# DSP.net
KiCad netlist of a schematic drawn in Altium Designer
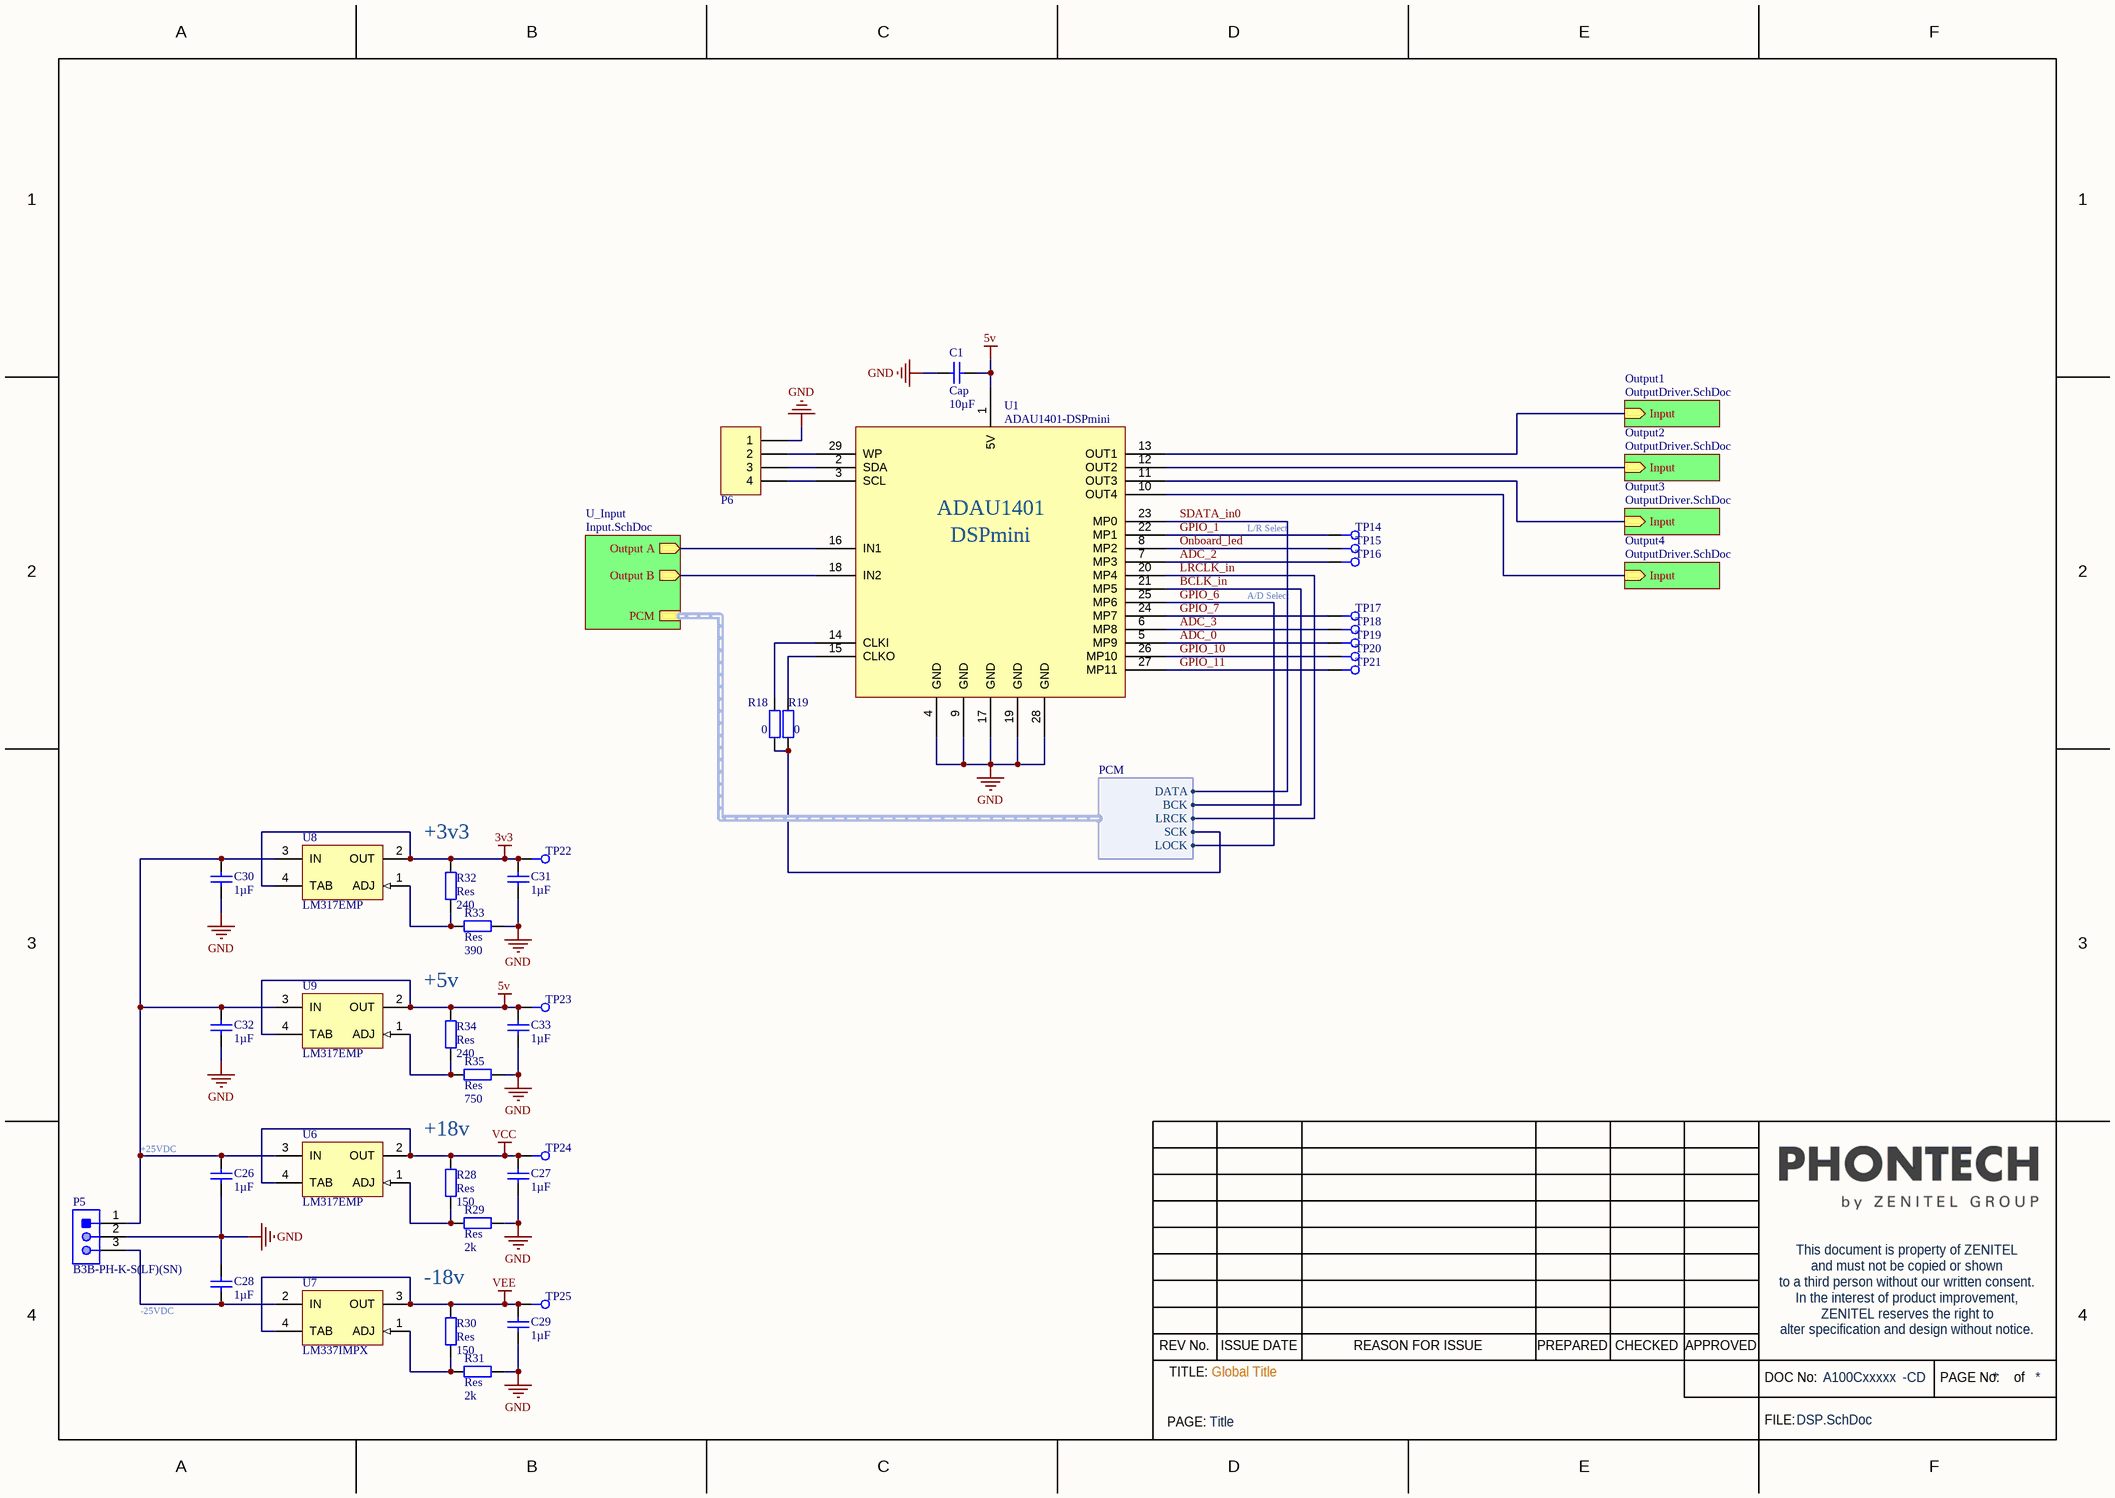
[diagram p0: DSP.SchDoc]

(export (version "E")
  (design (tool "Eeschema 10.0.6"))
  (components
    (comp (ref "C1")
      (value "Cap")
      (footprint "CAPC2013X140X50NL20T25")
      (description "CR0805 10u 10V X7R 10% h=1.25mm")
      (fields
        (field (name "ALTIUM_VALUE") "10µF")
        (field (name "TOLERANCE") "10%")
        (field (name "VOLTAGE") "10V")
      )
      (libsource (lib "Zenitel Concord PRO Vault") (part "Capacitor-IEC"))
    )
    (comp (ref "C26")
      (value "1µF")
      (footprint "CAPC3225N")
      (description "Chip cap 1uF 50v X7R 1210")
      (fields (field (name "TOLERANCE") "10%") (field (name "ZENITEL PARTNUMBER") "4000084277"))
      (libsource (lib "Zenitel Concord PRO Vault") (part "Capacitor-IEC"))
    )
    (comp (ref "C27")
      (value "1µF")
      (footprint "CAPC3225N")
      (description "Chip cap 1uF 50v X7R 1210")
      (fields (field (name "TOLERANCE") "10%") (field (name "ZENITEL PARTNUMBER") "4000084277"))
      (libsource (lib "Zenitel Concord PRO Vault") (part "Capacitor-IEC"))
    )
    (comp (ref "C28")
      (value "1µF")
      (footprint "CAPC3225N")
      (description "Chip cap 1uF 50v X7R 1210")
      (fields (field (name "TOLERANCE") "10%") (field (name "ZENITEL PARTNUMBER") "4000084277"))
      (libsource (lib "Zenitel Concord PRO Vault") (part "Capacitor-IEC"))
    )
    (comp (ref "C29")
      (value "1µF")
      (footprint "CAPC3225N")
      (description "Chip cap 1uF 50v X7R 1210")
      (fields (field (name "TOLERANCE") "10%") (field (name "ZENITEL PARTNUMBER") "4000084277"))
      (libsource (lib "Zenitel Concord PRO Vault") (part "Capacitor-IEC"))
    )
    (comp (ref "C30")
      (value "1µF")
      (footprint "CAPC3225N")
      (description "Chip cap 1uF 50v X7R 1210")
      (fields (field (name "TOLERANCE") "10%") (field (name "ZENITEL PARTNUMBER") "4000084277"))
      (libsource (lib "Zenitel Concord PRO Vault") (part "Capacitor-IEC"))
    )
    (comp (ref "C31")
      (value "1µF")
      (footprint "CAPC3225N")
      (description "Chip cap 1uF 50v X7R 1210")
      (fields (field (name "TOLERANCE") "10%") (field (name "ZENITEL PARTNUMBER") "4000084277"))
      (libsource (lib "Zenitel Concord PRO Vault") (part "Capacitor-IEC"))
    )
    (comp (ref "C32")
      (value "1µF")
      (footprint "CAPC3225N")
      (description "Chip cap 1uF 50v X7R 1210")
      (fields (field (name "TOLERANCE") "10%") (field (name "ZENITEL PARTNUMBER") "4000084277"))
      (libsource (lib "Zenitel Concord PRO Vault") (part "Capacitor-IEC"))
    )
    (comp (ref "C33")
      (value "1µF")
      (footprint "CAPC3225N")
      (description "Chip cap 1uF 50v X7R 1210")
      (fields (field (name "TOLERANCE") "10%") (field (name "ZENITEL PARTNUMBER") "4000084277"))
      (libsource (lib "Zenitel Concord PRO Vault") (part "Capacitor-IEC"))
    )
    (comp (ref "P5")
      (value "B3B-PH-K-S(LF)(SN)")
      (footprint "JST-B3B-PH-K-S-3_V")
      (fields (field (name "MANUFACTURER") "JST"))
      (libsource (lib "Altium Content Vault") (part "CN-1P-M-R3"))
    )
    (comp (ref "P6")
      (value "Header 4")
      (footprint "TSW-104-14-S-S")
      (description "4 Pin straight header")
      (fields (field (name "ZENITEL PARTNUMBER") "4000097756"))
      (libsource (lib "Zenitel Concord PRO Vault") (part "Header 4"))
    )
    (comp (ref "R18")
      (value "0")
      (footprint "RESC3216X60X45NL10T20")
      (description "0R 1206")
      (fields (field (name "ZENITEL PARTNUMBER") "4000085059") (field (name "POWER") "250mW"))
      (libsource (lib "") (part "Resistor-IEC_3"))
    )
    (comp (ref "R19")
      (value "0")
      (footprint "RESC3216X60X45NL10T20")
      (description "0R 1206")
      (fields (field (name "ZENITEL PARTNUMBER") "4000085059") (field (name "POWER") "250mW"))
      (libsource (lib "") (part "Resistor-IEC_3"))
    )
    (comp (ref "R28")
      (value "Res")
      (footprint "RESC1005X40X25NL05T05")
      (description "Chip resistor 150R - 0402")
      (fields
        (field (name "ALTIUM_VALUE") "150")
        (field (name "TOLERANCE") "1%")
        (field (name "POWER") "62.5mW")
      )
      (libsource (lib "") (part "Resistor-IEC_2"))
    )
    (comp (ref "R29")
      (value "Res")
      (footprint "RESC1005X40X25NL05T05")
      (description "Chip resistor 2k 1% - 0402")
      (fields
        (field (name "ALTIUM_VALUE") "2k")
        (field (name "TOLERANCE") "1%")
        (field (name "ZENITEL PARTNUMBER") "EGSMD80417")
      )
      (libsource (lib "") (part "Resistor-IEC_1"))
    )
    (comp (ref "R30")
      (value "Res")
      (footprint "RESC1005X40X25NL05T05")
      (description "Chip resistor 150R - 0402")
      (fields
        (field (name "ALTIUM_VALUE") "150")
        (field (name "TOLERANCE") "1%")
        (field (name "POWER") "62.5mW")
      )
      (libsource (lib "") (part "Resistor-IEC_2"))
    )
    (comp (ref "R31")
      (value "Res")
      (footprint "RESC1005X40X25NL05T05")
      (description "Chip resistor 2k 1% - 0402")
      (fields
        (field (name "ALTIUM_VALUE") "2k")
        (field (name "TOLERANCE") "1%")
        (field (name "ZENITEL PARTNUMBER") "EGSMD80417")
      )
      (libsource (lib "") (part "Resistor-IEC_1"))
    )
    (comp (ref "R32")
      (value "Res")
      (footprint "RESC1005X40X25NL05T05")
      (description "Chip resistor 240R 1% - 0402")
      (fields
        (field (name "ALTIUM_VALUE") "240")
        (field (name "VOLTAGE") "50V")
        (field (name "TOLERANCE") "1%")
      )
      (libsource (lib "") (part "Resistor-IEC_2"))
    )
    (comp (ref "R33")
      (value "Res")
      (footprint "RESC1005X40X25NL05T05")
      (description "Chip resistor 390R - 0402")
      (fields
        (field (name "ALTIUM_VALUE") "390")
        (field (name "TOLERANCE") "5%")
        (field (name "ZENITEL PARTNUMBER") "4000081083")
      )
      (libsource (lib "Zenitel Concord PRO Vault") (part "Resistor-IEC"))
    )
    (comp (ref "R34")
      (value "Res")
      (footprint "RESC1005X40X25NL05T05")
      (description "Chip resistor 240R 1% - 0402")
      (fields
        (field (name "ALTIUM_VALUE") "240")
        (field (name "VOLTAGE") "50V")
        (field (name "TOLERANCE") "1%")
      )
      (libsource (lib "") (part "Resistor-IEC_2"))
    )
    (comp (ref "R35")
      (value "Res")
      (footprint "RESC1005X40X25NL05T05")
      (description "Chip resistor 750R 1% - 0402")
      (fields
        (field (name "ALTIUM_VALUE") "750")
        (field (name "ZENITEL PARTNUMBER") "EGSMD80353")
        (field (name "VOLTAGE") "50V")
      )
      (libsource (lib "Zenitel Concord PRO Vault") (part "Resistor-IEC"))
    )
    (comp (ref "TP14")
      (value "TP Ø1.0MM")
      (footprint "TP_1MM")
      (description "Test Point, copper pad, 1.0mm diameter")
      (libsource (lib "Zenitel Concord PRO Vault") (part "Symbol"))
    )
    (comp (ref "TP15")
      (value "TP Ø1.0MM")
      (footprint "TP_1MM")
      (description "Test Point, copper pad, 1.0mm diameter")
      (libsource (lib "Zenitel Concord PRO Vault") (part "Symbol"))
    )
    (comp (ref "TP16")
      (value "TP Ø1.0MM")
      (footprint "TP_1MM")
      (description "Test Point, copper pad, 1.0mm diameter")
      (libsource (lib "Zenitel Concord PRO Vault") (part "Symbol"))
    )
    (comp (ref "TP17")
      (value "TP Ø1.0MM")
      (footprint "TP_1MM")
      (description "Test Point, copper pad, 1.0mm diameter")
      (libsource (lib "Zenitel Concord PRO Vault") (part "Symbol"))
    )
    (comp (ref "TP18")
      (value "TP Ø1.0MM")
      (footprint "TP_1MM")
      (description "Test Point, copper pad, 1.0mm diameter")
      (libsource (lib "Zenitel Concord PRO Vault") (part "Symbol"))
    )
    (comp (ref "TP19")
      (value "TP Ø1.0MM")
      (footprint "TP_1MM")
      (description "Test Point, copper pad, 1.0mm diameter")
      (libsource (lib "Zenitel Concord PRO Vault") (part "Symbol"))
    )
    (comp (ref "TP20")
      (value "TP Ø1.0MM")
      (footprint "TP_1MM")
      (description "Test Point, copper pad, 1.0mm diameter")
      (libsource (lib "Zenitel Concord PRO Vault") (part "Symbol"))
    )
    (comp (ref "TP21")
      (value "TP Ø1.0MM")
      (footprint "TP_1MM")
      (description "Test Point, copper pad, 1.0mm diameter")
      (libsource (lib "Zenitel Concord PRO Vault") (part "Symbol"))
    )
    (comp (ref "TP22")
      (value "TP Ø1.0MM")
      (footprint "TP_1MM")
      (description "Test Point, copper pad, 1.0mm diameter")
      (libsource (lib "Zenitel Concord PRO Vault") (part "Symbol"))
    )
    (comp (ref "TP23")
      (value "TP Ø1.0MM")
      (footprint "TP_1MM")
      (description "Test Point, copper pad, 1.0mm diameter")
      (libsource (lib "Zenitel Concord PRO Vault") (part "Symbol"))
    )
    (comp (ref "TP24")
      (value "TP Ø1.0MM")
      (footprint "TP_1MM")
      (description "Test Point, copper pad, 1.0mm diameter")
      (libsource (lib "Zenitel Concord PRO Vault") (part "Symbol"))
    )
    (comp (ref "TP25")
      (value "TP Ø1.0MM")
      (footprint "TP_1MM")
      (description "Test Point, copper pad, 1.0mm diameter")
      (libsource (lib "Zenitel Concord PRO Vault") (part "Symbol"))
    )
    (comp (ref "U1")
      (value "ADAU1401-DSPmini")
      (footprint "ADAU1401-DSPmini")
      (libsource (lib "ADAU1401-DSPmini") (part "ADAU1401-DSPmini"))
    )
    (comp (ref "U6")
      (value "LM317EMP")
      (footprint "SOT223-4N")
      (description "LM317EMP SOT223")
      (fields (field (name "ZENITEL PARTNUMBER") "4000084254"))
      (libsource (lib "Zenitel Concord PRO Vault") (part "LM317EMP"))
    )
    (comp (ref "U7")
      (value "LM337IMPX")
      (footprint "DCY0004A_N")
      (description "3-Terminal Adjustable Negative Regulator, 4-pin SOT-223")
      (fields (field (name "MANUFACTURER") "Texas Instruments"))
      (libsource (lib "Altium Content Vault") (part "PM-REG-LM337ADJ-SOT4"))
    )
    (comp (ref "U8")
      (value "LM317EMP")
      (footprint "SOT223-4N")
      (description "LM317EMP SOT223")
      (fields (field (name "ZENITEL PARTNUMBER") "4000084254"))
      (libsource (lib "Zenitel Concord PRO Vault") (part "LM317EMP"))
    )
    (comp (ref "U9")
      (value "LM317EMP")
      (footprint "SOT223-4N")
      (description "LM317EMP SOT223")
      (fields (field (name "ZENITEL PARTNUMBER") "4000084254"))
      (libsource (lib "Zenitel Concord PRO Vault") (part "LM317EMP"))
    )
  )
  (nets
    (net (code "2") (name "/ADC_0") (class "Default")
      (node (ref "TP19") (pin "1") (pinfunction "1_1") (pintype "passive"))
      (node (ref "U1") (pin "5") (pinfunction "MP9_5") (pintype "passive"))
    )
    (net (code "3") (name "/ADC_2") (class "Default")
      (node (ref "TP16") (pin "1") (pinfunction "1_1") (pintype "passive"))
      (node (ref "U1") (pin "7") (pinfunction "MP3_7") (pintype "passive"))
    )
    (net (code "4") (name "/ADC_3") (class "Default")
      (node (ref "TP18") (pin "1") (pinfunction "1_1") (pintype "passive"))
      (node (ref "U1") (pin "6") (pinfunction "MP8_6") (pintype "passive"))
    )
    (net (code "5") (name "/BCLK_in") (class "Default")
      (node (ref "U1") (pin "21") (pinfunction "MP5_21") (pintype "passive"))
    )
    (net (code "6") (name "/GPIO_1") (class "Default")
      (node (ref "TP14") (pin "1") (pinfunction "1_1") (pintype "passive"))
      (node (ref "U1") (pin "22") (pinfunction "MP1_22") (pintype "passive"))
    )
    (net (code "7") (name "/GPIO_6") (class "Default")
      (node (ref "U1") (pin "25") (pinfunction "MP6_25") (pintype "passive"))
    )
    (net (code "8") (name "/GPIO_7") (class "Default")
      (node (ref "TP17") (pin "1") (pinfunction "1_1") (pintype "passive"))
      (node (ref "U1") (pin "24") (pinfunction "MP7_24") (pintype "passive"))
    )
    (net (code "9") (name "/GPIO_10") (class "Default")
      (node (ref "TP20") (pin "1") (pinfunction "1_1") (pintype "passive"))
      (node (ref "U1") (pin "26") (pinfunction "MP10_26") (pintype "passive"))
    )
    (net (code "10") (name "/GPIO_11") (class "Default")
      (node (ref "TP21") (pin "1") (pinfunction "1_1") (pintype "passive"))
      (node (ref "U1") (pin "27") (pinfunction "MP11_27") (pintype "passive"))
    )
    (net (code "11") (name "/Input") (class "Default")
      (node (ref "U1") (pin "12") (pinfunction "OUT2_12") (pintype "passive"))
    )
    (net (code "12") (name "/Input_1") (class "Default")
      (node (ref "U1") (pin "13") (pinfunction "OUT1_13") (pintype "passive"))
    )
    (net (code "13") (name "/Input_2") (class "Default")
      (node (ref "U1") (pin "11") (pinfunction "OUT3_11") (pintype "passive"))
    )
    (net (code "14") (name "/Input_3") (class "Default")
      (node (ref "U1") (pin "10") (pinfunction "OUT4_10") (pintype "passive"))
    )
    (net (code "15") (name "/LRCLK_in") (class "Default")
      (node (ref "U1") (pin "20") (pinfunction "MP4_20") (pintype "passive"))
    )
    (net (code "16") (name "/Onboard_led") (class "Default")
      (node (ref "TP15") (pin "1") (pinfunction "1_1") (pintype "passive"))
      (node (ref "U1") (pin "8") (pinfunction "MP2_8") (pintype "passive"))
    )
    (net (code "17") (name "/Output A") (class "Default")
      (node (ref "U1") (pin "16") (pinfunction "IN1_16") (pintype "passive"))
    )
    (net (code "18") (name "/Output B") (class "Default")
      (node (ref "U1") (pin "18") (pinfunction "IN2_18") (pintype "passive"))
    )
    (net (code "19") (name "/SDATA_in0") (class "Default")
      (node (ref "U1") (pin "23") (pinfunction "MP0_23") (pintype "passive"))
    )
    (net (code "21") (name "3v3") (class "Default")
      (node (ref "C31") (pin "2") (pinfunction "2_2") (pintype "passive"))
      (node (ref "R32") (pin "2") (pinfunction "2_2") (pintype "passive"))
      (node (ref "TP22") (pin "1") (pinfunction "1_1") (pintype "passive"))
      (node (ref "U8") (pin "2") (pinfunction "OUT_2") (pintype "power_in"))
      (node (ref "U8") (pin "4") (pinfunction "TAB_4") (pintype "power_in"))
    )
    (net (code "22") (name "5v") (class "Default")
      (node (ref "C1") (pin "2") (pinfunction "2_2") (pintype "passive"))
      (node (ref "C33") (pin "2") (pinfunction "2_2") (pintype "passive"))
      (node (ref "R34") (pin "2") (pinfunction "2_2") (pintype "passive"))
      (node (ref "TP23") (pin "1") (pinfunction "1_1") (pintype "passive"))
      (node (ref "U1") (pin "1") (pinfunction "5V_1") (pintype "power_in"))
      (node (ref "U9") (pin "2") (pinfunction "OUT_2") (pintype "power_in"))
      (node (ref "U9") (pin "4") (pinfunction "TAB_4") (pintype "power_in"))
    )
    (net (code "23") (name "GND") (class "Default")
      (node (ref "C1") (pin "1") (pinfunction "1_1") (pintype "passive"))
      (node (ref "C26") (pin "1") (pinfunction "1_1") (pintype "passive"))
      (node (ref "C27") (pin "1") (pinfunction "1_1") (pintype "passive"))
      (node (ref "C28") (pin "2") (pinfunction "2_2") (pintype "passive"))
      (node (ref "C29") (pin "1") (pinfunction "1_1") (pintype "passive"))
      (node (ref "C30") (pin "1") (pinfunction "1_1") (pintype "passive"))
      (node (ref "C31") (pin "1") (pinfunction "1_1") (pintype "passive"))
      (node (ref "C32") (pin "1") (pinfunction "1_1") (pintype "passive"))
      (node (ref "C33") (pin "1") (pinfunction "1_1") (pintype "passive"))
      (node (ref "P5") (pin "2") (pinfunction "2_2") (pintype "passive"))
      (node (ref "P6") (pin "1") (pinfunction "1_1") (pintype "passive"))
      (node (ref "R29") (pin "1") (pinfunction "1_1") (pintype "passive"))
      (node (ref "R31") (pin "1") (pinfunction "1_1") (pintype "passive"))
      (node (ref "R33") (pin "2") (pinfunction "2_2") (pintype "passive"))
      (node (ref "R35") (pin "2") (pinfunction "2_2") (pintype "passive"))
      (node (ref "U1") (pin "17") (pinfunction "GND_17") (pintype "power_in"))
      (node (ref "U1") (pin "19") (pinfunction "GND_19") (pintype "power_in"))
      (node (ref "U1") (pin "28") (pinfunction "GND_28") (pintype "power_in"))
      (node (ref "U1") (pin "4") (pinfunction "GND_4") (pintype "power_in"))
      (node (ref "U1") (pin "9") (pinfunction "GND_9") (pintype "power_in"))
    )
    (net (code "24") (name "Net-(R18-Pad2)") (class "Default")
      (node (ref "R18") (pin "2") (pinfunction "2_2") (pintype "passive"))
      (node (ref "R19") (pin "2") (pinfunction "2_2") (pintype "passive"))
    )
    (net (code "25") (name "Net-(U1-CLKI)") (class "Default")
      (node (ref "R18") (pin "1") (pinfunction "1_1") (pintype "passive"))
      (node (ref "U1") (pin "14") (pinfunction "CLKI_14") (pintype "passive"))
    )
    (net (code "26") (name "Net-(U1-CLKO)") (class "Default")
      (node (ref "R19") (pin "1") (pinfunction "1_1") (pintype "passive"))
      (node (ref "U1") (pin "15") (pinfunction "CLKO_15") (pintype "passive"))
    )
    (net (code "27") (name "Net-(U1-SCL)") (class "Default")
      (node (ref "P6") (pin "4") (pinfunction "4_4") (pintype "passive"))
      (node (ref "U1") (pin "3") (pinfunction "SCL_3") (pintype "passive"))
    )
    (net (code "28") (name "Net-(U1-SDA)") (class "Default")
      (node (ref "P6") (pin "3") (pinfunction "3_3") (pintype "passive"))
      (node (ref "U1") (pin "2") (pinfunction "SDA_2") (pintype "passive"))
    )
    (net (code "29") (name "Net-(U1-WP)") (class "Default")
      (node (ref "P6") (pin "2") (pinfunction "2_2") (pintype "passive"))
      (node (ref "U1") (pin "29") (pinfunction "WP_29") (pintype "passive"))
    )
    (net (code "30") (name "Net-(U6-ADJ)") (class "Default")
      (node (ref "R28") (pin "1") (pinfunction "1_1") (pintype "passive"))
      (node (ref "R29") (pin "2") (pinfunction "2_2") (pintype "passive"))
      (node (ref "U6") (pin "1") (pinfunction "ADJ_1") (pintype "input"))
    )
    (net (code "31") (name "Net-(U6-IN)") (class "Default")
      (node (ref "C26") (pin "2") (pinfunction "2_2") (pintype "passive"))
      (node (ref "C30") (pin "2") (pinfunction "2_2") (pintype "passive"))
      (node (ref "C32") (pin "2") (pinfunction "2_2") (pintype "passive"))
      (node (ref "P5") (pin "1") (pinfunction "1_1") (pintype "passive"))
      (node (ref "U6") (pin "3") (pinfunction "IN_3") (pintype "power_in"))
      (node (ref "U8") (pin "3") (pinfunction "IN_3") (pintype "power_in"))
      (node (ref "U9") (pin "3") (pinfunction "IN_3") (pintype "power_in"))
    )
    (net (code "32") (name "Net-(U7-ADJ)") (class "Default")
      (node (ref "R30") (pin "1") (pinfunction "1_1") (pintype "passive"))
      (node (ref "R31") (pin "2") (pinfunction "2_2") (pintype "passive"))
      (node (ref "U7") (pin "1") (pinfunction "ADJ_1") (pintype "input"))
    )
    (net (code "33") (name "Net-(U7-IN)") (class "Default")
      (node (ref "C28") (pin "1") (pinfunction "1_1") (pintype "passive"))
      (node (ref "P5") (pin "3") (pinfunction "3_3") (pintype "passive"))
      (node (ref "U7") (pin "2") (pinfunction "IN_2") (pintype "power_in"))
    )
    (net (code "34") (name "Net-(U8-ADJ)") (class "Default")
      (node (ref "R32") (pin "1") (pinfunction "1_1") (pintype "passive"))
      (node (ref "R33") (pin "1") (pinfunction "1_1") (pintype "passive"))
      (node (ref "U8") (pin "1") (pinfunction "ADJ_1") (pintype "input"))
    )
    (net (code "35") (name "Net-(U9-ADJ)") (class "Default")
      (node (ref "R34") (pin "1") (pinfunction "1_1") (pintype "passive"))
      (node (ref "R35") (pin "1") (pinfunction "1_1") (pintype "passive"))
      (node (ref "U9") (pin "1") (pinfunction "ADJ_1") (pintype "input"))
    )
    (net (code "36") (name "VCC") (class "Default")
      (node (ref "C27") (pin "2") (pinfunction "2_2") (pintype "passive"))
      (node (ref "R28") (pin "2") (pinfunction "2_2") (pintype "passive"))
      (node (ref "TP24") (pin "1") (pinfunction "1_1") (pintype "passive"))
      (node (ref "U6") (pin "2") (pinfunction "OUT_2") (pintype "power_in"))
      (node (ref "U6") (pin "4") (pinfunction "TAB_4") (pintype "power_in"))
    )
    (net (code "37") (name "VEE") (class "Default")
      (node (ref "C29") (pin "2") (pinfunction "2_2") (pintype "passive"))
      (node (ref "R30") (pin "2") (pinfunction "2_2") (pintype "passive"))
      (node (ref "TP25") (pin "1") (pinfunction "1_1") (pintype "passive"))
      (node (ref "U7") (pin "3") (pinfunction "OUT_3") (pintype "power_in"))
      (node (ref "U7") (pin "4") (pinfunction "TAB_4") (pintype "power_in"))
    )
  )
)
